# sd9_redraw.net
KiCad netlist of a schematic drawn in EAGLE
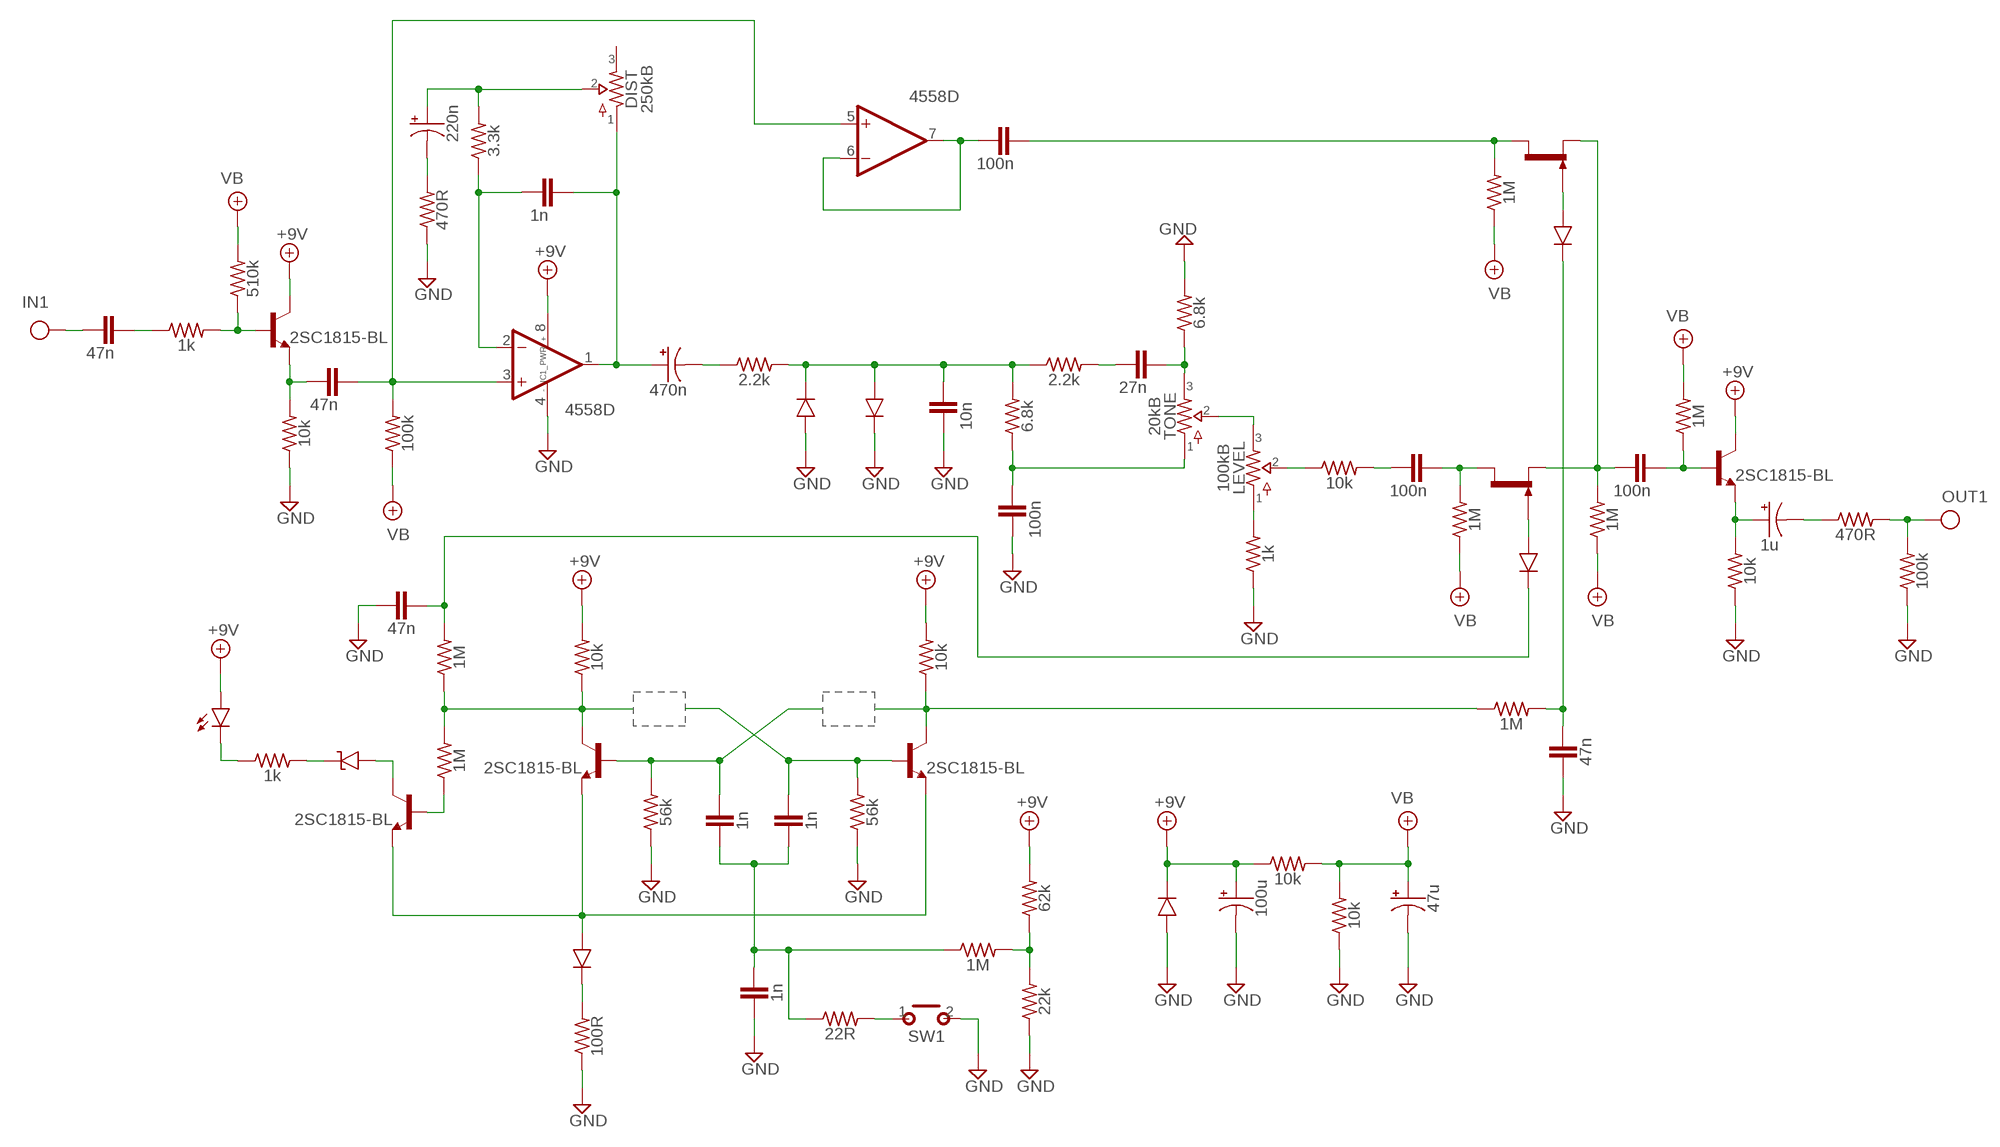
[diagram p0: schematic, sheet 1]

(export (version "E")
  (design (tool "Eeschema 10.0.6"))
  (components
    (comp (ref "C1")
      (value "100u")
      (footprint "eagle-import:050_020")
      (libsource (lib "eagle-import") (part "0500"))
    )
    (comp (ref "C2")
      (value "47u")
      (footprint "eagle-import:050_020")
      (libsource (lib "eagle-import") (part "0500"))
    )
    (comp (ref "C3")
      (value "47n")
      (footprint "eagle-import:BOX_SMALL")
      (libsource (lib "eagle-import") (part "CER/FILMBOX.1"))
    )
    (comp (ref "C4")
      (value "47n")
      (footprint "eagle-import:BOX_SMALL")
      (libsource (lib "eagle-import") (part "CER/FILMBOX.1"))
    )
    (comp (ref "C5")
      (value "1n")
      (footprint "eagle-import:BOX_SMALL")
      (libsource (lib "eagle-import") (part "CER/FILMBOX.1"))
    )
    (comp (ref "C6")
      (value "220n")
      (footprint "eagle-import:050_020")
      (libsource (lib "eagle-import") (part "0500"))
    )
    (comp (ref "C7")
      (value "470n")
      (footprint "eagle-import:050_020")
      (libsource (lib "eagle-import") (part "0500"))
    )
    (comp (ref "C8")
      (value "10n")
      (footprint "eagle-import:BOX_SMALL")
      (libsource (lib "eagle-import") (part "CER/FILMBOX.1"))
    )
    (comp (ref "C9")
      (value "100n")
      (footprint "eagle-import:BOX_SMALL")
      (libsource (lib "eagle-import") (part "CER/FILMBOX.1"))
    )
    (comp (ref "C10")
      (value "27n")
      (footprint "eagle-import:BOX_SMALL")
      (libsource (lib "eagle-import") (part "CER/FILMBOX.1"))
    )
    (comp (ref "C11")
      (value "100n")
      (footprint "eagle-import:BOX_SMALL")
      (libsource (lib "eagle-import") (part "CER/FILMBOX.1"))
    )
    (comp (ref "C12")
      (value "100n")
      (footprint "eagle-import:BOX_SMALL")
      (libsource (lib "eagle-import") (part "CER/FILMBOX.1"))
    )
    (comp (ref "C13")
      (value "1u")
      (footprint "eagle-import:050_020")
      (libsource (lib "eagle-import") (part "0500"))
    )
    (comp (ref "C14")
      (value "1n")
      (footprint "eagle-import:BOX_SMALL")
      (libsource (lib "eagle-import") (part "CER/FILMBOX.1"))
    )
    (comp (ref "C15")
      (value "100n")
      (footprint "eagle-import:BOX_SMALL")
      (libsource (lib "eagle-import") (part "CER/FILMBOX.1"))
    )
    (comp (ref "C30")
      (value "47n")
      (footprint "eagle-import:BOX_SMALL")
      (libsource (lib "eagle-import") (part "CER/FILMBOX.1"))
    )
    (comp (ref "C32")
      (value "1n")
      (footprint "eagle-import:BOX_SMALL")
      (libsource (lib "eagle-import") (part "CER/FILMBOX.1"))
    )
    (comp (ref "C34")
      (value "1n")
      (footprint "eagle-import:BOX_SMALL")
      (libsource (lib "eagle-import") (part "CER/FILMBOX.1"))
    )
    (comp (ref "C36")
      (value "47n")
      (footprint "eagle-import:BOX_SMALL")
      (libsource (lib "eagle-import") (part "CER/FILMBOX.1"))
    )
    (comp (ref "D1")
      (value "DO41.2")
      (footprint "eagle-import:DO41-2")
      (libsource (lib "eagle-import") (part "DO41.2"))
    )
    (comp (ref "D2")
      (value "DO41.2")
      (footprint "eagle-import:DO41-2")
      (libsource (lib "eagle-import") (part "DO41.2"))
    )
    (comp (ref "D3")
      (value "DO41.2")
      (footprint "eagle-import:DO41-2")
      (libsource (lib "eagle-import") (part "DO41.2"))
    )
    (comp (ref "D4")
      (value "DO41.2")
      (footprint "eagle-import:DO41-2")
      (libsource (lib "eagle-import") (part "DO41.2"))
    )
    (comp (ref "D5")
      (value "DO41.2")
      (footprint "eagle-import:DO41-2")
      (libsource (lib "eagle-import") (part "DO41.2"))
    )
    (comp (ref "D6")
      (value "DO41.2")
      (footprint "eagle-import:DO41-2")
      (libsource (lib "eagle-import") (part "DO41.2"))
    )
    (comp (ref "D7")
      (value "ZENER.2")
      (footprint "eagle-import:DO41-2")
      (libsource (lib "eagle-import") (part "ZENER.2"))
    )
    (comp (ref "D8")
      (value "LED")
      (footprint "eagle-import:3MM_D")
      (libsource (lib "eagle-import") (part "LED"))
    )
    (comp (ref "DIST")
      (value "250kB")
      (footprint "eagle-import:16MM")
      (libsource (lib "eagle-import") (part "POTS16MM"))
    )
    (comp (ref "IC1")
      (value "4558D")
      (footprint "eagle-import:DIL0")
      (libsource (lib "eagle-import") (part "DUALTH"))
    )
    (comp (ref "LEVEL")
      (value "100kB")
      (footprint "eagle-import:16MM")
      (libsource (lib "eagle-import") (part "POTS16MM"))
    )
    (comp (ref "Q1")
      (value "2SC1815-BL")
      (footprint "eagle-import:TO92-")
      (libsource (lib "eagle-import") (part "2N3904"))
    )
    (comp (ref "Q2")
      (value "2SK30A-Y")
      (footprint "eagle-import:TO92-")
      (libsource (lib "eagle-import") (part "2SK170"))
    )
    (comp (ref "Q3")
      (value "2SK30A-Y")
      (footprint "eagle-import:TO92-")
      (libsource (lib "eagle-import") (part "2SK170"))
    )
    (comp (ref "Q4")
      (value "2SC1815-BL")
      (footprint "eagle-import:TO92-")
      (libsource (lib "eagle-import") (part "2N3904"))
    )
    (comp (ref "Q5")
      (value "2SC1815-BL")
      (footprint "eagle-import:TO92-")
      (libsource (lib "eagle-import") (part "2SC828A"))
    )
    (comp (ref "Q30")
      (value "2SC1815-BL")
      (footprint "eagle-import:TO92-")
      (libsource (lib "eagle-import") (part "2SC828A"))
    )
    (comp (ref "Q31")
      (value "2SC1815-BL")
      (footprint "eagle-import:TO92-")
      (libsource (lib "eagle-import") (part "2SC828A"))
    )
    (comp (ref "R1")
      (value "10k")
      (footprint "eagle-import:R0207_3")
      (libsource (lib "eagle-import") (part "R_.3B"))
    )
    (comp (ref "R2")
      (value "10k")
      (footprint "eagle-import:R0207_3")
      (libsource (lib "eagle-import") (part "R_.3B"))
    )
    (comp (ref "R3")
      (value "1k")
      (footprint "eagle-import:R0207_3")
      (libsource (lib "eagle-import") (part "R_.3B"))
    )
    (comp (ref "R4")
      (value "510k")
      (footprint "eagle-import:R0207_3")
      (libsource (lib "eagle-import") (part "R_.3B"))
    )
    (comp (ref "R5")
      (value "10k")
      (footprint "eagle-import:R0207_3")
      (libsource (lib "eagle-import") (part "R_.3B"))
    )
    (comp (ref "R6")
      (value "100k")
      (footprint "eagle-import:R0207_3")
      (libsource (lib "eagle-import") (part "R_.3B"))
    )
    (comp (ref "R7")
      (value "3.3k")
      (footprint "eagle-import:R0207_3")
      (libsource (lib "eagle-import") (part "R_.3B"))
    )
    (comp (ref "R8")
      (value "470R")
      (footprint "eagle-import:R0207_3")
      (libsource (lib "eagle-import") (part "R_.3B"))
    )
    (comp (ref "R9")
      (value "2.2k")
      (footprint "eagle-import:R0207_3")
      (libsource (lib "eagle-import") (part "R_.3B"))
    )
    (comp (ref "R10")
      (value "2.2k")
      (footprint "eagle-import:R0207_3")
      (libsource (lib "eagle-import") (part "R_.3B"))
    )
    (comp (ref "R11")
      (value "6.8k")
      (footprint "eagle-import:R0207_3")
      (libsource (lib "eagle-import") (part "R_.3B"))
    )
    (comp (ref "R12")
      (value "6.8k")
      (footprint "eagle-import:R0207_3")
      (libsource (lib "eagle-import") (part "R_.3B"))
    )
    (comp (ref "R13")
      (value "1M")
      (footprint "eagle-import:R0207_3")
      (libsource (lib "eagle-import") (part "R_.3B"))
    )
    (comp (ref "R14")
      (value "1M")
      (footprint "eagle-import:R0207_3")
      (libsource (lib "eagle-import") (part "R_.3B"))
    )
    (comp (ref "R15")
      (value "1M")
      (footprint "eagle-import:R0207_3")
      (libsource (lib "eagle-import") (part "R_.3B"))
    )
    (comp (ref "R16")
      (value "1M")
      (footprint "eagle-import:R0207_3")
      (libsource (lib "eagle-import") (part "R_.3B"))
    )
    (comp (ref "R17")
      (value "10k")
      (footprint "eagle-import:R0207_3")
      (libsource (lib "eagle-import") (part "R_.3B"))
    )
    (comp (ref "R18")
      (value "470R")
      (footprint "eagle-import:R0207_3")
      (libsource (lib "eagle-import") (part "R_.3B"))
    )
    (comp (ref "R19")
      (value "100k")
      (footprint "eagle-import:R0207_3")
      (libsource (lib "eagle-import") (part "R_.3B"))
    )
    (comp (ref "R20")
      (value "22R")
      (footprint "eagle-import:R0207_3")
      (libsource (lib "eagle-import") (part "R_.3B"))
    )
    (comp (ref "R21")
      (value "1M")
      (footprint "eagle-import:R0207_3")
      (libsource (lib "eagle-import") (part "R_.3B"))
    )
    (comp (ref "R22")
      (value "62k")
      (footprint "eagle-import:R0207_3")
      (libsource (lib "eagle-import") (part "R_.3B"))
    )
    (comp (ref "R23")
      (value "22k")
      (footprint "eagle-import:R0207_3")
      (libsource (lib "eagle-import") (part "R_.3B"))
    )
    (comp (ref "R24")
      (value "100R")
      (footprint "eagle-import:R0207_3")
      (libsource (lib "eagle-import") (part "R_.3B"))
    )
    (comp (ref "R25")
      (value "1M")
      (footprint "eagle-import:R0207_3")
      (libsource (lib "eagle-import") (part "R_.3B"))
    )
    (comp (ref "R26")
      (value "1k")
      (footprint "eagle-import:R0207_3")
      (libsource (lib "eagle-import") (part "R_.3B"))
    )
    (comp (ref "R27")
      (value "1k")
      (footprint "eagle-import:R0207_3")
      (libsource (lib "eagle-import") (part "R_.3B"))
    )
    (comp (ref "R28")
      (value "10k")
      (footprint "eagle-import:R0207_3")
      (libsource (lib "eagle-import") (part "R_.3B"))
    )
    (comp (ref "R60")
      (value "1M")
      (footprint "eagle-import:R0207_3")
      (libsource (lib "eagle-import") (part "R_.3B"))
    )
    (comp (ref "R61")
      (value "10k")
      (footprint "eagle-import:R0207_3")
      (libsource (lib "eagle-import") (part "R_.3B"))
    )
    (comp (ref "R62")
      (value "56k")
      (footprint "eagle-import:R0207_3")
      (libsource (lib "eagle-import") (part "R_.3B"))
    )
    (comp (ref "R65")
      (value "56k")
      (footprint "eagle-import:R0207_3")
      (libsource (lib "eagle-import") (part "R_.3B"))
    )
    (comp (ref "R66")
      (value "10k")
      (footprint "eagle-import:R0207_3")
      (libsource (lib "eagle-import") (part "R_.3B"))
    )
    (comp (ref "R69")
      (value "1M")
      (footprint "eagle-import:R0207_3")
      (libsource (lib "eagle-import") (part "R_.3B"))
    )
    (comp (ref "SW1")
      (value "MOMENTARY")
      (footprint "eagle-import:SPST")
      (libsource (lib "eagle-import") (part "MOMENTARY"))
    )
    (comp (ref "TONE")
      (value "20kB")
      (footprint "eagle-import:16MM")
      (libsource (lib "eagle-import") (part "POTS16MM"))
    )
  )
  (nets
    (net (code "1") (name "+9V") (class "Default")
      (node (ref "C1") (pin "+") (pinfunction "+_+") (pintype "passive"))
      (node (ref "D1") (pin "C") (pinfunction "C_C") (pintype "passive"))
      (node (ref "D8") (pin "ANODE") (pinfunction "A_ANODE") (pintype "passive"))
      (node (ref "IC1") (pin "8") (pinfunction "V+_8") (pintype "power_in"))
      (node (ref "Q1") (pin "1") (pinfunction "C_1") (pintype "passive"))
      (node (ref "Q4") (pin "1") (pinfunction "C_1") (pintype "passive"))
      (node (ref "R1") (pin "1") (pinfunction "1_1") (pintype "passive"))
      (node (ref "R22") (pin "2") (pinfunction "2_2") (pintype "passive"))
      (node (ref "R61") (pin "2") (pinfunction "2_2") (pintype "passive"))
      (node (ref "R66") (pin "2") (pinfunction "2_2") (pintype "passive"))
    )
    (net (code "2") (name "GND") (class "Default")
      (node (ref "C1") (pin "-") (pinfunction "-_-") (pintype "passive"))
      (node (ref "C14") (pin "2") (pinfunction "2_2") (pintype "passive"))
      (node (ref "C2") (pin "-") (pinfunction "-_-") (pintype "passive"))
      (node (ref "C30") (pin "2") (pinfunction "2_2") (pintype "passive"))
      (node (ref "C36") (pin "2") (pinfunction "2_2") (pintype "passive"))
      (node (ref "C8") (pin "2") (pinfunction "2_2") (pintype "passive"))
      (node (ref "C9") (pin "2") (pinfunction "2_2") (pintype "passive"))
      (node (ref "D1") (pin "A") (pinfunction "A_A") (pintype "passive"))
      (node (ref "D2") (pin "A") (pinfunction "A_A") (pintype "passive"))
      (node (ref "D3") (pin "C") (pinfunction "C_C") (pintype "passive"))
      (node (ref "IC1") (pin "4") (pinfunction "V-_4") (pintype "power_in"))
      (node (ref "R12") (pin "2") (pinfunction "2_2") (pintype "passive"))
      (node (ref "R17") (pin "1") (pinfunction "1_1") (pintype "passive"))
      (node (ref "R19") (pin "1") (pinfunction "1_1") (pintype "passive"))
      (node (ref "R2") (pin "1") (pinfunction "1_1") (pintype "passive"))
      (node (ref "R23") (pin "1") (pinfunction "1_1") (pintype "passive"))
      (node (ref "R24") (pin "1") (pinfunction "1_1") (pintype "passive"))
      (node (ref "R27") (pin "1") (pinfunction "1_1") (pintype "passive"))
      (node (ref "R5") (pin "1") (pinfunction "1_1") (pintype "passive"))
      (node (ref "R62") (pin "1") (pinfunction "1_1") (pintype "passive"))
      (node (ref "R65") (pin "1") (pinfunction "1_1") (pintype "passive"))
      (node (ref "R8") (pin "1") (pinfunction "1_1") (pintype "passive"))
      (node (ref "SW1") (pin "2") (pinfunction "S_2") (pintype "passive"))
    )
    (net (code "3") (name "IN") (class "Default")
      (node (ref "C3") (pin "2") (pinfunction "2_2") (pintype "passive"))
    )
    (net (code "4") (name "Net-(C3-Pad1)") (class "Default")
      (node (ref "C3") (pin "1") (pinfunction "1_1") (pintype "passive"))
      (node (ref "R3") (pin "1") (pinfunction "1_1") (pintype "passive"))
    )
    (net (code "5") (name "Net-(C6-Pad+)") (class "Default")
      (node (ref "C6") (pin "+") (pinfunction "+_+") (pintype "passive"))
      (node (ref "DIST") (pin "2") (pinfunction "2_2") (pintype "passive"))
      (node (ref "R7") (pin "2") (pinfunction "2_2") (pintype "passive"))
    )
    (net (code "6") (name "Net-(C6-Pad-)") (class "Default")
      (node (ref "C6") (pin "-") (pinfunction "-_-") (pintype "passive"))
      (node (ref "R8") (pin "2") (pinfunction "2_2") (pintype "passive"))
    )
    (net (code "7") (name "Net-(C7-Pad-)") (class "Default")
      (node (ref "C7") (pin "-") (pinfunction "-_-") (pintype "passive"))
      (node (ref "R9") (pin "1") (pinfunction "1_1") (pintype "passive"))
    )
    (net (code "8") (name "Net-(C8-Pad1)") (class "Default")
      (node (ref "C8") (pin "1") (pinfunction "1_1") (pintype "passive"))
      (node (ref "D2") (pin "C") (pinfunction "C_C") (pintype "passive"))
      (node (ref "D3") (pin "A") (pinfunction "A_A") (pintype "passive"))
      (node (ref "R10") (pin "1") (pinfunction "1_1") (pintype "passive"))
      (node (ref "R11") (pin "2") (pinfunction "2_2") (pintype "passive"))
      (node (ref "R9") (pin "2") (pinfunction "2_2") (pintype "passive"))
    )
    (net (code "9") (name "Net-(C9-Pad1)") (class "Default")
      (node (ref "C9") (pin "1") (pinfunction "1_1") (pintype "passive"))
      (node (ref "R11") (pin "1") (pinfunction "1_1") (pintype "passive"))
      (node (ref "TONE") (pin "1") (pinfunction "1_1") (pintype "passive"))
    )
    (net (code "10") (name "Net-(C10-Pad1)") (class "Default")
      (node (ref "C10") (pin "1") (pinfunction "1_1") (pintype "passive"))
      (node (ref "R12") (pin "1") (pinfunction "1_1") (pintype "passive"))
      (node (ref "TONE") (pin "3") (pinfunction "3_3") (pintype "passive"))
    )
    (net (code "11") (name "Net-(C10-Pad2)") (class "Default")
      (node (ref "C10") (pin "2") (pinfunction "2_2") (pintype "passive"))
      (node (ref "R10") (pin "2") (pinfunction "2_2") (pintype "passive"))
    )
    (net (code "12") (name "Net-(C13-Pad-)") (class "Default")
      (node (ref "C13") (pin "-") (pinfunction "-_-") (pintype "passive"))
      (node (ref "R18") (pin "1") (pinfunction "1_1") (pintype "passive"))
    )
    (net (code "13") (name "Net-(C14-Pad1)") (class "Default")
      (node (ref "C14") (pin "1") (pinfunction "1_1") (pintype "passive"))
      (node (ref "C32") (pin "2") (pinfunction "2_2") (pintype "passive"))
      (node (ref "C34") (pin "2") (pinfunction "2_2") (pintype "passive"))
      (node (ref "R20") (pin "1") (pinfunction "1_1") (pintype "passive"))
      (node (ref "R21") (pin "1") (pinfunction "1_1") (pintype "passive"))
    )
    (net (code "14") (name "Net-(C15-Pad2)") (class "Default")
      (node (ref "C15") (pin "2") (pinfunction "2_2") (pintype "passive"))
      (node (ref "R28") (pin "2") (pinfunction "2_2") (pintype "passive"))
    )
    (net (code "15") (name "Net-(C30-Pad1)") (class "Default")
      (node (ref "C30") (pin "1") (pinfunction "1_1") (pintype "passive"))
      (node (ref "D5") (pin "C") (pinfunction "C_C") (pintype "passive"))
      (node (ref "R60") (pin "2") (pinfunction "2_2") (pintype "passive"))
    )
    (net (code "16") (name "Net-(C36-Pad1)") (class "Default")
      (node (ref "C36") (pin "1") (pinfunction "1_1") (pintype "passive"))
      (node (ref "D4") (pin "C") (pinfunction "C_C") (pintype "passive"))
      (node (ref "R69") (pin "2") (pinfunction "2_2") (pintype "passive"))
    )
    (net (code "17") (name "Net-(D6-PadC)") (class "Default")
      (node (ref "D6") (pin "C") (pinfunction "C_C") (pintype "passive"))
      (node (ref "R24") (pin "2") (pinfunction "2_2") (pintype "passive"))
    )
    (net (code "18") (name "Net-(D7-PadC)") (class "Default")
      (node (ref "D7") (pin "C") (pinfunction "C_C") (pintype "passive"))
      (node (ref "R26") (pin "2") (pinfunction "2_2") (pintype "passive"))
    )
    (net (code "19") (name "Net-(D8-C)") (class "Default")
      (node (ref "D8") (pin "P$1") (pinfunction "C_P$1") (pintype "passive"))
      (node (ref "R26") (pin "1") (pinfunction "1_1") (pintype "passive"))
    )
    (net (code "20") (name "Net-(IC1A-+IN)") (class "Default")
      (node (ref "C4") (pin "1") (pinfunction "1_1") (pintype "passive"))
      (node (ref "IC1") (pin "3") (pinfunction "+IN_3") (pintype "input"))
      (node (ref "IC1") (pin "5") (pinfunction "+IN_5") (pintype "input"))
      (node (ref "R6") (pin "2") (pinfunction "2_2") (pintype "passive"))
    )
    (net (code "21") (name "Net-(IC1A--IN)") (class "Default")
      (node (ref "C5") (pin "2") (pinfunction "2_2") (pintype "passive"))
      (node (ref "IC1") (pin "2") (pinfunction "-IN_2") (pintype "input"))
      (node (ref "R7") (pin "1") (pinfunction "1_1") (pintype "passive"))
    )
    (net (code "22") (name "Net-(IC1A-OUT)") (class "Default")
      (node (ref "C5") (pin "1") (pinfunction "1_1") (pintype "passive"))
      (node (ref "C7") (pin "+") (pinfunction "+_+") (pintype "passive"))
      (node (ref "DIST") (pin "1") (pinfunction "1_1") (pintype "passive"))
      (node (ref "IC1") (pin "1") (pinfunction "OUT_1") (pintype "output"))
    )
    (net (code "23") (name "Net-(IC1B--IN)") (class "Default")
      (node (ref "C11") (pin "2") (pinfunction "2_2") (pintype "passive"))
      (node (ref "IC1") (pin "6") (pinfunction "-IN_6") (pintype "input"))
      (node (ref "IC1") (pin "7") (pinfunction "OUT_7") (pintype "output"))
    )
    (net (code "24") (name "Net-(LEVEL-Pad1)") (class "Default")
      (node (ref "LEVEL") (pin "1") (pinfunction "1_1") (pintype "passive"))
      (node (ref "R27") (pin "2") (pinfunction "2_2") (pintype "passive"))
    )
    (net (code "25") (name "Net-(LEVEL-Pad2)") (class "Default")
      (node (ref "LEVEL") (pin "2") (pinfunction "2_2") (pintype "passive"))
      (node (ref "R28") (pin "1") (pinfunction "1_1") (pintype "passive"))
    )
    (net (code "26") (name "Net-(LEVEL-Pad3)") (class "Default")
      (node (ref "LEVEL") (pin "3") (pinfunction "3_3") (pintype "passive"))
      (node (ref "TONE") (pin "2") (pinfunction "2_2") (pintype "passive"))
    )
    (net (code "27") (name "Net-(Q1-B)") (class "Default")
      (node (ref "Q1") (pin "2") (pinfunction "B_2") (pintype "passive"))
      (node (ref "R3") (pin "2") (pinfunction "2_2") (pintype "passive"))
      (node (ref "R4") (pin "1") (pinfunction "1_1") (pintype "passive"))
    )
    (net (code "28") (name "Net-(Q1-E)") (class "Default")
      (node (ref "C4") (pin "2") (pinfunction "2_2") (pintype "passive"))
      (node (ref "Q1") (pin "3") (pinfunction "E_3") (pintype "passive"))
      (node (ref "R5") (pin "2") (pinfunction "2_2") (pintype "passive"))
    )
    (net (code "29") (name "Net-(Q2-D)") (class "Default")
      (node (ref "C15") (pin "1") (pinfunction "1_1") (pintype "passive"))
      (node (ref "Q2") (pin "3") (pinfunction "D_3") (pintype "passive"))
      (node (ref "R13") (pin "2") (pinfunction "2_2") (pintype "passive"))
    )
    (net (code "30") (name "Net-(Q2-G)") (class "Default")
      (node (ref "D5") (pin "A") (pinfunction "A_A") (pintype "passive"))
      (node (ref "Q2") (pin "2") (pinfunction "G_2") (pintype "passive"))
    )
    (net (code "31") (name "Net-(Q2-S)") (class "Default")
      (node (ref "C12") (pin "2") (pinfunction "2_2") (pintype "passive"))
      (node (ref "Q2") (pin "1") (pinfunction "S_1") (pintype "passive"))
      (node (ref "Q3") (pin "1") (pinfunction "S_1") (pintype "passive"))
      (node (ref "R14") (pin "2") (pinfunction "2_2") (pintype "passive"))
    )
    (net (code "32") (name "Net-(Q3-D)") (class "Default")
      (node (ref "C11") (pin "1") (pinfunction "1_1") (pintype "passive"))
      (node (ref "Q3") (pin "3") (pinfunction "D_3") (pintype "passive"))
      (node (ref "R15") (pin "2") (pinfunction "2_2") (pintype "passive"))
    )
    (net (code "33") (name "Net-(Q3-G)") (class "Default")
      (node (ref "D4") (pin "A") (pinfunction "A_A") (pintype "passive"))
      (node (ref "Q3") (pin "2") (pinfunction "G_2") (pintype "passive"))
    )
    (net (code "34") (name "Net-(Q4-B)") (class "Default")
      (node (ref "C12") (pin "1") (pinfunction "1_1") (pintype "passive"))
      (node (ref "Q4") (pin "2") (pinfunction "B_2") (pintype "passive"))
      (node (ref "R16") (pin "1") (pinfunction "1_1") (pintype "passive"))
    )
    (net (code "35") (name "Net-(Q4-E)") (class "Default")
      (node (ref "C13") (pin "+") (pinfunction "+_+") (pintype "passive"))
      (node (ref "Q4") (pin "3") (pinfunction "E_3") (pintype "passive"))
      (node (ref "R17") (pin "2") (pinfunction "2_2") (pintype "passive"))
    )
    (net (code "36") (name "Net-(Q5-B)") (class "Default")
      (node (ref "Q5") (pin "1") (pinfunction "B_1") (pintype "passive"))
      (node (ref "R25") (pin "1") (pinfunction "1_1") (pintype "passive"))
    )
    (net (code "37") (name "Net-(Q5-C)") (class "Default")
      (node (ref "D7") (pin "A") (pinfunction "A_A") (pintype "passive"))
      (node (ref "Q5") (pin "2") (pinfunction "C_2") (pintype "passive"))
    )
    (net (code "38") (name "Net-(Q30-B)") (class "Default")
      (node (ref "C32") (pin "1") (pinfunction "1_1") (pintype "passive"))
      (node (ref "Q30") (pin "1") (pinfunction "B_1") (pintype "passive"))
      (node (ref "R62") (pin "2") (pinfunction "2_2") (pintype "passive"))
    )
    (net (code "39") (name "Net-(Q30-C)") (class "Default")
      (node (ref "Q30") (pin "2") (pinfunction "C_2") (pintype "passive"))
      (node (ref "R25") (pin "2") (pinfunction "2_2") (pintype "passive"))
      (node (ref "R60") (pin "1") (pinfunction "1_1") (pintype "passive"))
      (node (ref "R61") (pin "1") (pinfunction "1_1") (pintype "passive"))
    )
    (net (code "40") (name "Net-(Q30-E)") (class "Default")
      (node (ref "D6") (pin "A") (pinfunction "A_A") (pintype "passive"))
      (node (ref "Q30") (pin "3") (pinfunction "E_3") (pintype "passive"))
      (node (ref "Q31") (pin "3") (pinfunction "E_3") (pintype "passive"))
      (node (ref "Q5") (pin "3") (pinfunction "E_3") (pintype "passive"))
    )
    (net (code "41") (name "Net-(Q31-B)") (class "Default")
      (node (ref "C34") (pin "1") (pinfunction "1_1") (pintype "passive"))
      (node (ref "Q31") (pin "1") (pinfunction "B_1") (pintype "passive"))
      (node (ref "R65") (pin "2") (pinfunction "2_2") (pintype "passive"))
    )
    (net (code "42") (name "Net-(Q31-C)") (class "Default")
      (node (ref "Q31") (pin "2") (pinfunction "C_2") (pintype "passive"))
      (node (ref "R66") (pin "1") (pinfunction "1_1") (pintype "passive"))
      (node (ref "R69") (pin "1") (pinfunction "1_1") (pintype "passive"))
    )
    (net (code "43") (name "Net-(R21-Pad2)") (class "Default")
      (node (ref "R21") (pin "2") (pinfunction "2_2") (pintype "passive"))
      (node (ref "R22") (pin "1") (pinfunction "1_1") (pintype "passive"))
      (node (ref "R23") (pin "2") (pinfunction "2_2") (pintype "passive"))
    )
    (net (code "44") (name "Net-(SW1-P)") (class "Default")
      (node (ref "R20") (pin "2") (pinfunction "2_2") (pintype "passive"))
      (node (ref "SW1") (pin "1") (pinfunction "P_1") (pintype "passive"))
    )
    (net (code "45") (name "OUT") (class "Default")
      (node (ref "R18") (pin "2") (pinfunction "2_2") (pintype "passive"))
      (node (ref "R19") (pin "2") (pinfunction "2_2") (pintype "passive"))
    )
    (net (code "46") (name "VB") (class "Default")
      (node (ref "C2") (pin "+") (pinfunction "+_+") (pintype "passive"))
      (node (ref "R1") (pin "2") (pinfunction "2_2") (pintype "passive"))
      (node (ref "R13") (pin "1") (pinfunction "1_1") (pintype "passive"))
      (node (ref "R14") (pin "1") (pinfunction "1_1") (pintype "passive"))
      (node (ref "R15") (pin "1") (pinfunction "1_1") (pintype "passive"))
      (node (ref "R16") (pin "2") (pinfunction "2_2") (pintype "passive"))
      (node (ref "R2") (pin "2") (pinfunction "2_2") (pintype "passive"))
      (node (ref "R4") (pin "2") (pinfunction "2_2") (pintype "passive"))
      (node (ref "R6") (pin "1") (pinfunction "1_1") (pintype "passive"))
    )
    (net (code "47") (name "unconnected-(DIST-Pad3)") (class "Default")
      (node (ref "DIST") (pin "3") (pinfunction "3_3") (pintype "passive"))
    )
  )
)
